# stm32-2inch40-usb-sd.net
KiCad netlist of a schematic drawn in EAGLE
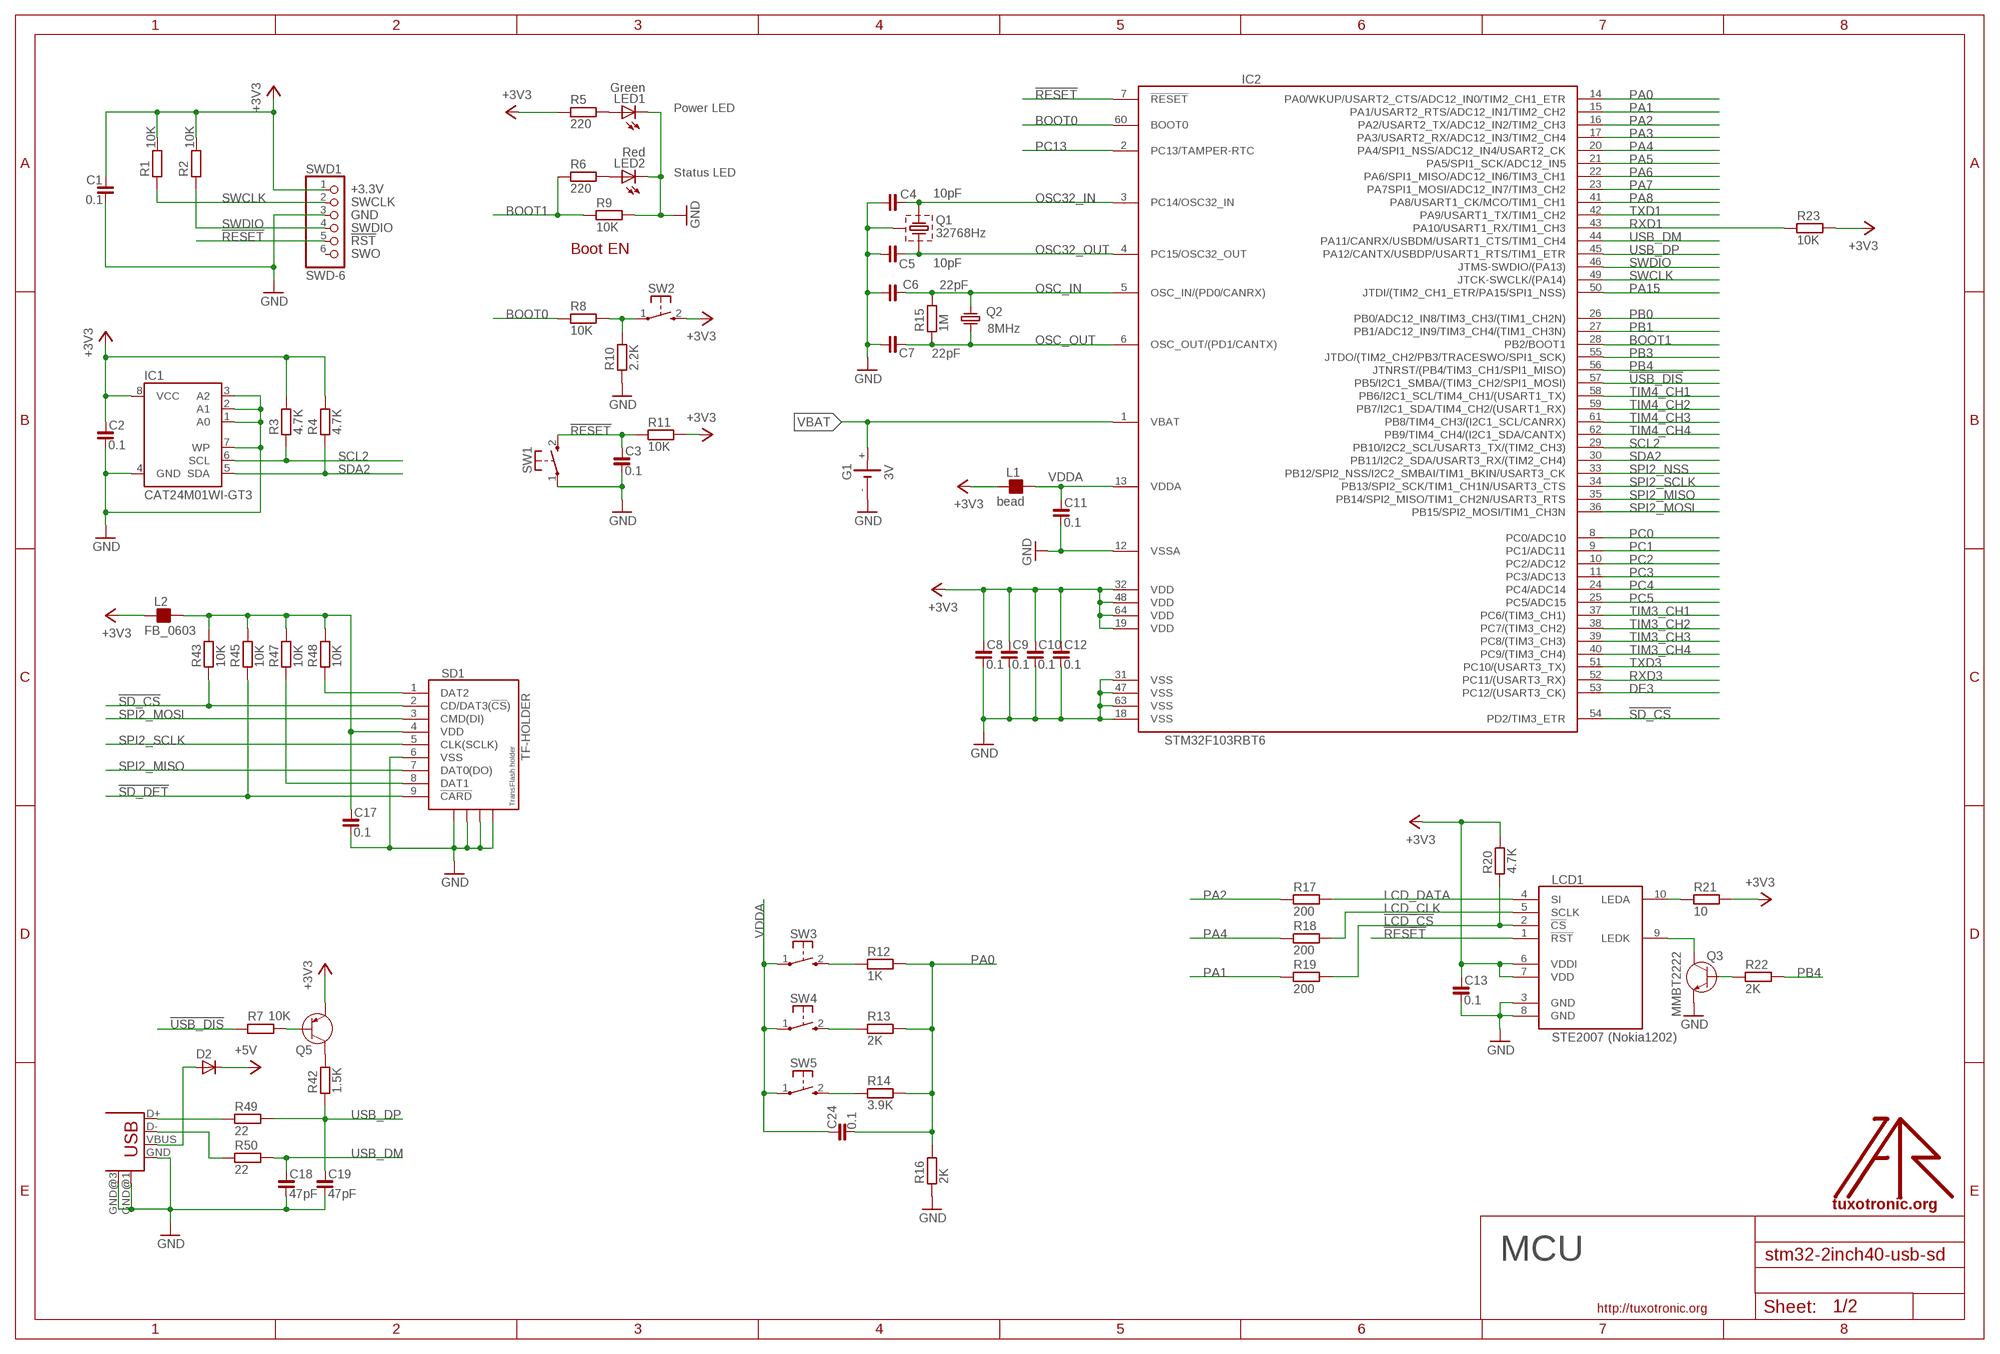
[diagram p0: schematic, sheet 1]
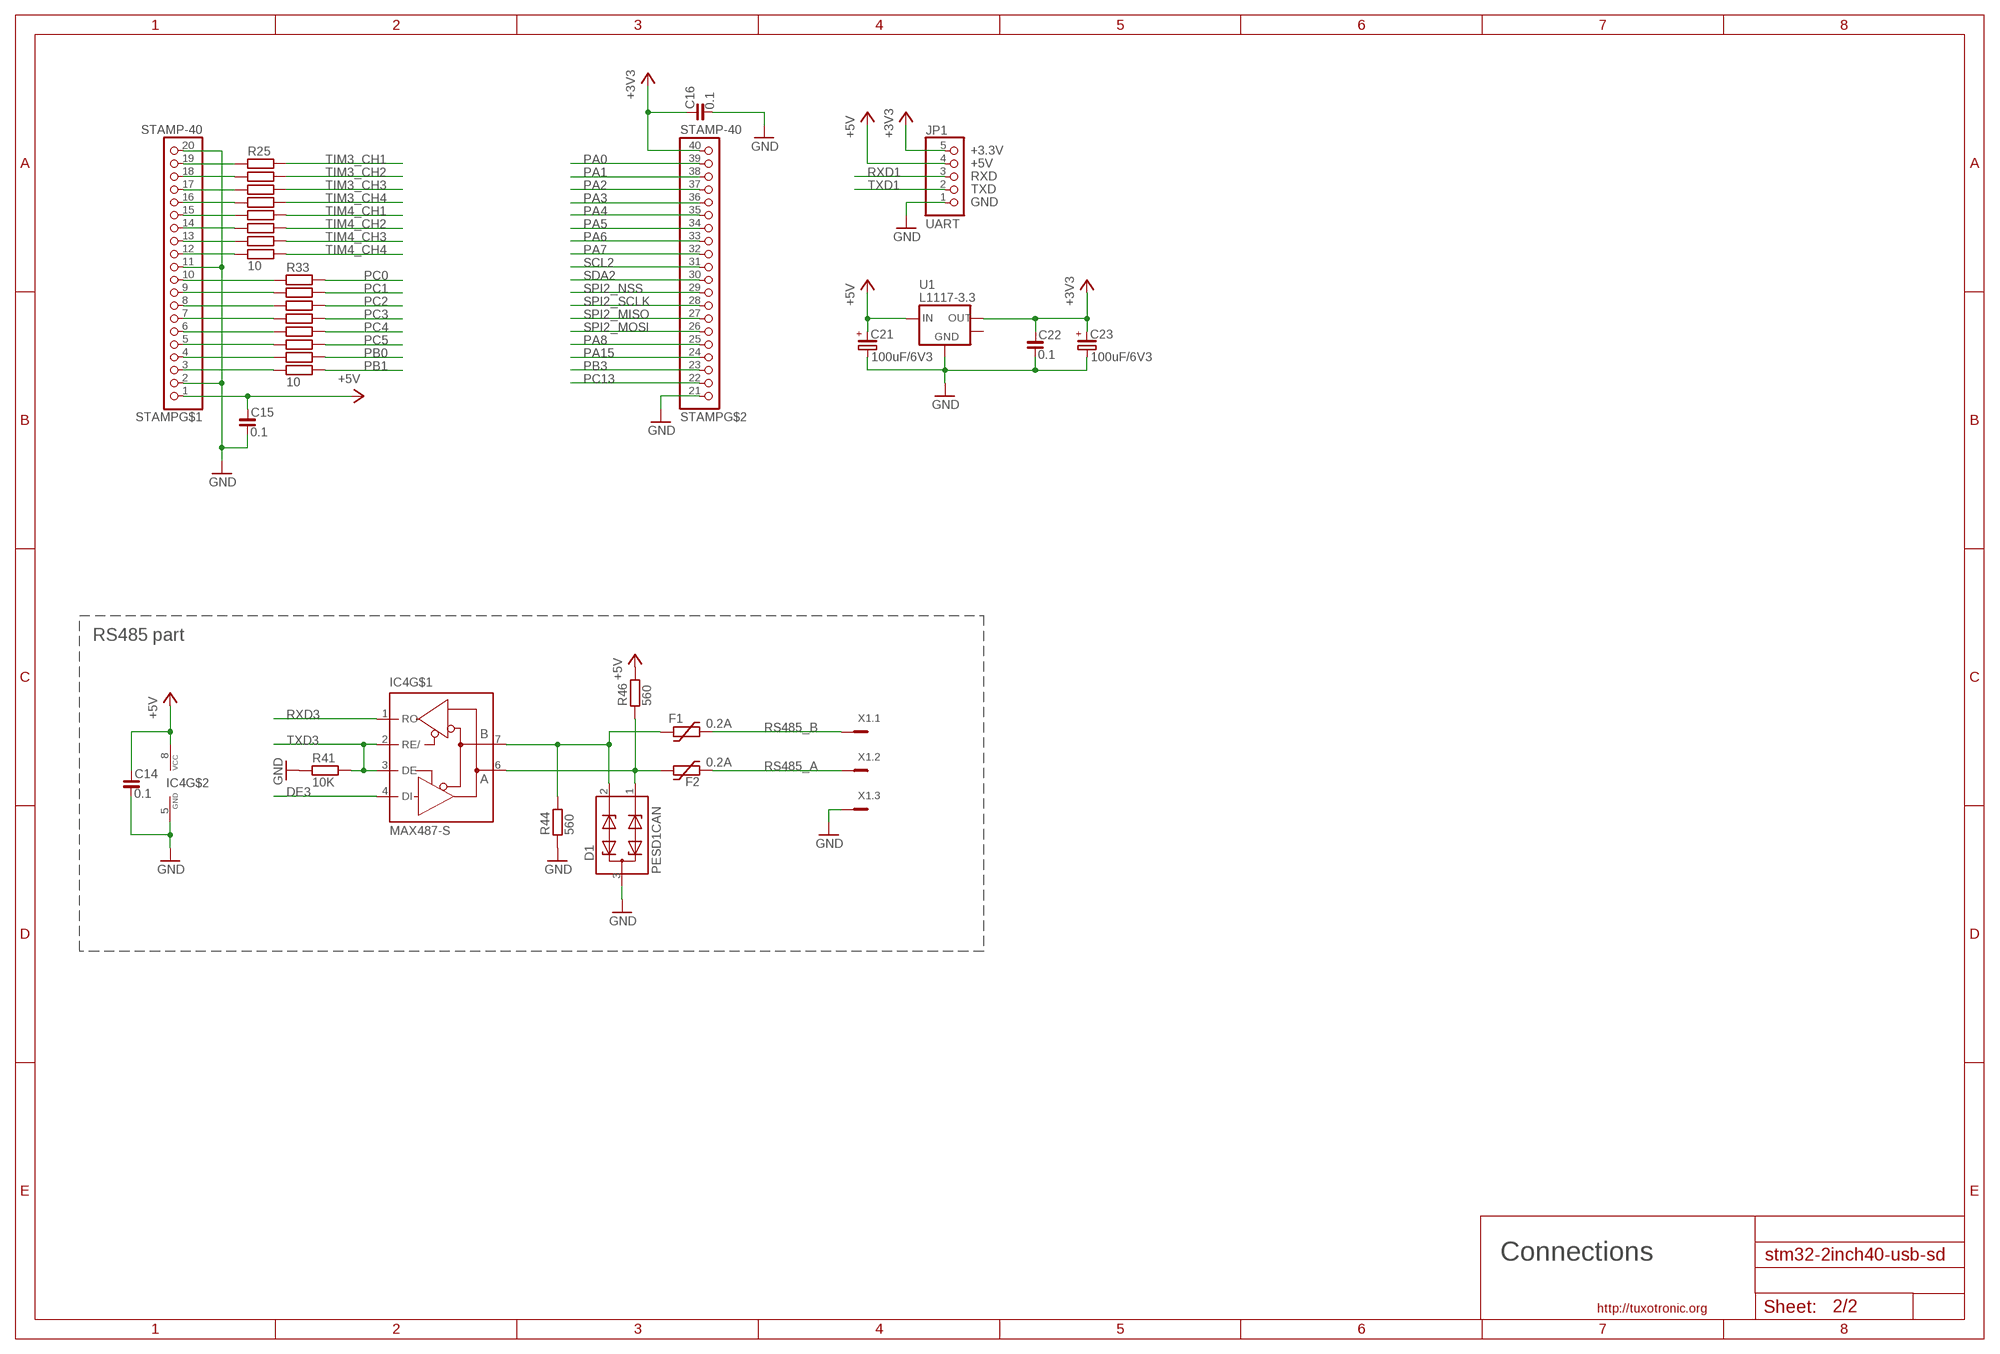
[diagram p1: schematic, sheet 2]

(export (version "E")
  (design (tool "Eeschema 10.0.6"))
  (components
    (comp (ref "C14")
      (value "0.1")
      (footprint "eagle-import:C0603")
      (libsource (lib "eagle-import") (part "C_0603"))
    )
    (comp (ref "C15")
      (value "0.1")
      (footprint "eagle-import:C0805")
      (libsource (lib "eagle-import") (part "C_0805"))
    )
    (comp (ref "C16")
      (value "0.1")
      (footprint "eagle-import:C0805")
      (libsource (lib "eagle-import") (part "C_0805"))
    )
    (comp (ref "C21")
      (value "100uF/6V3")
      (footprint "eagle-import:SMC_D")
      (libsource (lib "eagle-import") (part "CP_SMCD"))
    )
    (comp (ref "C22")
      (value "0.1")
      (footprint "eagle-import:C0805")
      (libsource (lib "eagle-import") (part "C_0805"))
    )
    (comp (ref "C23")
      (value "100uF/6V3")
      (footprint "eagle-import:SMC_D")
      (libsource (lib "eagle-import") (part "CP_SMCD"))
    )
    (comp (ref "D1")
      (value "PESD1CAN")
      (footprint "eagle-import:SOT23")
      (libsource (lib "eagle-import") (part "PESD1CAN"))
    )
    (comp (ref "F1")
      (value "0.2A")
      (footprint "eagle-import:1206L")
      (libsource (lib "eagle-import") (part "1206L"))
    )
    (comp (ref "F2")
      (value "0.2A")
      (footprint "eagle-import:1206L")
      (libsource (lib "eagle-import") (part "1206L"))
    )
    (comp (ref "IC4")
      (value "MAX487-S")
      (footprint "eagle-import:SO08")
      (libsource (lib "eagle-import") (part "MAX487-S"))
    )
    (comp (ref "JP1")
      (value "UART")
      (footprint "eagle-import:UART_1X05")
      (libsource (lib "eagle-import") (part "UART-5_2.54"))
    )
    (comp (ref "R25")
      (value "10")
      (footprint "eagle-import:R0603")
      (libsource (lib "eagle-import") (part "R_0603"))
    )
    (comp (ref "R26")
      (value "10")
      (footprint "eagle-import:R0603")
      (libsource (lib "eagle-import") (part "R_0603"))
    )
    (comp (ref "R27")
      (value "10")
      (footprint "eagle-import:R0603")
      (libsource (lib "eagle-import") (part "R_0603"))
    )
    (comp (ref "R28")
      (value "10")
      (footprint "eagle-import:R0603")
      (libsource (lib "eagle-import") (part "R_0603"))
    )
    (comp (ref "R29")
      (value "10")
      (footprint "eagle-import:R0603")
      (libsource (lib "eagle-import") (part "R_0603"))
    )
    (comp (ref "R30")
      (value "10")
      (footprint "eagle-import:R0603")
      (libsource (lib "eagle-import") (part "R_0603"))
    )
    (comp (ref "R31")
      (value "10")
      (footprint "eagle-import:R0603")
      (libsource (lib "eagle-import") (part "R_0603"))
    )
    (comp (ref "R32")
      (value "10")
      (footprint "eagle-import:R0603")
      (libsource (lib "eagle-import") (part "R_0603"))
    )
    (comp (ref "R33")
      (value "10")
      (footprint "eagle-import:R0603")
      (libsource (lib "eagle-import") (part "R_0603"))
    )
    (comp (ref "R34")
      (value "10")
      (footprint "eagle-import:R0603")
      (libsource (lib "eagle-import") (part "R_0603"))
    )
    (comp (ref "R35")
      (value "10")
      (footprint "eagle-import:R0603")
      (libsource (lib "eagle-import") (part "R_0603"))
    )
    (comp (ref "R36")
      (value "10")
      (footprint "eagle-import:R0603")
      (libsource (lib "eagle-import") (part "R_0603"))
    )
    (comp (ref "R37")
      (value "10")
      (footprint "eagle-import:R0603")
      (libsource (lib "eagle-import") (part "R_0603"))
    )
    (comp (ref "R38")
      (value "10")
      (footprint "eagle-import:R0603")
      (libsource (lib "eagle-import") (part "R_0603"))
    )
    (comp (ref "R39")
      (value "10")
      (footprint "eagle-import:R0603")
      (libsource (lib "eagle-import") (part "R_0603"))
    )
    (comp (ref "R40")
      (value "10")
      (footprint "eagle-import:R0603")
      (libsource (lib "eagle-import") (part "R_0603"))
    )
    (comp (ref "R41")
      (value "10K")
      (footprint "eagle-import:R0603")
      (libsource (lib "eagle-import") (part "R_0603"))
    )
    (comp (ref "R44")
      (value "560")
      (footprint "eagle-import:R0603")
      (libsource (lib "eagle-import") (part "R_0603"))
    )
    (comp (ref "R46")
      (value "560")
      (footprint "eagle-import:R0603")
      (libsource (lib "eagle-import") (part "R_0603"))
    )
    (comp (ref "STAMP")
      (value "STAMP-40")
      (footprint "eagle-import:STAMP-40")
      (libsource (lib "eagle-import") (part "STAMP-40"))
    )
    (comp (ref "U1")
      (value "L1117-3.3")
      (footprint "eagle-import:SOT223")
      (libsource (lib "eagle-import") (part "LM1117-3.3"))
    )
    (comp (ref "X1")
      (value "MCV3")
      (footprint "eagle-import:MCV3")
      (libsource (lib "eagle-import") (part "MCV3"))
    )
    (comp (ref "C1")
      (value "0.1")
      (footprint "eagle-import:C0603")
      (libsource (lib "eagle-import") (part "C_0603"))
    )
    (comp (ref "C2")
      (value "0.1")
      (footprint "eagle-import:C0603")
      (libsource (lib "eagle-import") (part "C_0603"))
    )
    (comp (ref "C3")
      (value "0.1")
      (footprint "eagle-import:C0603")
      (libsource (lib "eagle-import") (part "C_0603"))
    )
    (comp (ref "C4")
      (value "10pF")
      (footprint "eagle-import:C0603")
      (libsource (lib "eagle-import") (part "C_0603"))
    )
    (comp (ref "C5")
      (value "10pF")
      (footprint "eagle-import:C0603")
      (libsource (lib "eagle-import") (part "C_0603"))
    )
    (comp (ref "C6")
      (value "22pF")
      (footprint "eagle-import:C0603")
      (libsource (lib "eagle-import") (part "C_0603"))
    )
    (comp (ref "C7")
      (value "22pF")
      (footprint "eagle-import:C0603")
      (libsource (lib "eagle-import") (part "C_0603"))
    )
    (comp (ref "C8")
      (value "0.1")
      (footprint "eagle-import:C0603")
      (libsource (lib "eagle-import") (part "C_0603"))
    )
    (comp (ref "C9")
      (value "0.1")
      (footprint "eagle-import:C0603")
      (libsource (lib "eagle-import") (part "C_0603"))
    )
    (comp (ref "C10")
      (value "0.1")
      (footprint "eagle-import:C0603")
      (libsource (lib "eagle-import") (part "C_0603"))
    )
    (comp (ref "C11")
      (value "0.1")
      (footprint "eagle-import:C0603")
      (libsource (lib "eagle-import") (part "C_0603"))
    )
    (comp (ref "C12")
      (value "0.1")
      (footprint "eagle-import:C0603")
      (libsource (lib "eagle-import") (part "C_0603"))
    )
    (comp (ref "C13")
      (value "0.1")
      (footprint "eagle-import:C0603")
      (libsource (lib "eagle-import") (part "C_0603"))
    )
    (comp (ref "C17")
      (value "0.1")
      (footprint "eagle-import:C0603")
      (libsource (lib "eagle-import") (part "C_0603"))
    )
    (comp (ref "C18")
      (value "47pF")
      (footprint "eagle-import:C0603")
      (libsource (lib "eagle-import") (part "C_0603"))
    )
    (comp (ref "C19")
      (value "47pF")
      (footprint "eagle-import:C0603")
      (libsource (lib "eagle-import") (part "C_0603"))
    )
    (comp (ref "C24")
      (value "0.1")
      (footprint "eagle-import:C0603")
      (libsource (lib "eagle-import") (part "C_0603"))
    )
    (comp (ref "D2")
      (value "D-SOD-87")
      (footprint "eagle-import:SOD87")
      (libsource (lib "eagle-import") (part "D-SOD-87"))
    )
    (comp (ref "G1")
      (value "3V")
      (footprint "eagle-import:SMT1220")
      (libsource (lib "eagle-import") (part "1220SMT"))
    )
    (comp (ref "IC1")
      (value "CAT24M01WI-GT3")
      (footprint "eagle-import:SO08")
      (libsource (lib "eagle-import") (part "AT24CS256"))
    )
    (comp (ref "IC2")
      (value "STM32F103RBT6")
      (footprint "eagle-import:TQFP64")
      (libsource (lib "eagle-import") (part "STM32F103R"))
    )
    (comp (ref "L1")
      (value "bead")
      (footprint "eagle-import:L0603")
      (libsource (lib "eagle-import") (part "FB_0603"))
    )
    (comp (ref "L2")
      (value "FB_0603")
      (footprint "eagle-import:L0603")
      (libsource (lib "eagle-import") (part "FB_0603"))
    )
    (comp (ref "LCD1")
      (value "STE2007 (Nokia1202)")
      (footprint "eagle-import:NOKIA1202LCD-EXT")
      (libsource (lib "eagle-import") (part "LCD1202-EXT"))
    )
    (comp (ref "LED1")
      (value "Green")
      (footprint "eagle-import:CHIP-LED0805")
      (libsource (lib "eagle-import") (part "LEDCHIP-LED0805"))
    )
    (comp (ref "LED2")
      (value "Red")
      (footprint "eagle-import:CHIP-LED0805")
      (libsource (lib "eagle-import") (part "LEDCHIP-LED0805"))
    )
    (comp (ref "Q1")
      (value "32768Hz")
      (footprint "eagle-import:TC38H-G")
      (libsource (lib "eagle-import") (part "CRSTL3-"))
    )
    (comp (ref "Q2")
      (value "8MHz")
      (footprint "eagle-import:HC49_S")
      (libsource (lib "eagle-import") (part "CRYSTAL-HC49S"))
    )
    (comp (ref "Q3")
      (value "MMBT2222")
      (footprint "eagle-import:SOT23")
      (libsource (lib "eagle-import") (part "MMBT2222"))
    )
    (comp (ref "Q5")
      (value "PNP-SOT23")
      (footprint "eagle-import:SOT23")
      (libsource (lib "eagle-import") (part "PNP-SOT23"))
    )
    (comp (ref "R1")
      (value "10K")
      (footprint "eagle-import:R0603")
      (libsource (lib "eagle-import") (part "R_0603"))
    )
    (comp (ref "R2")
      (value "10K")
      (footprint "eagle-import:R0603")
      (libsource (lib "eagle-import") (part "R_0603"))
    )
    (comp (ref "R3")
      (value "4.7K")
      (footprint "eagle-import:R0603")
      (libsource (lib "eagle-import") (part "R_0603"))
    )
    (comp (ref "R4")
      (value "4.7K")
      (footprint "eagle-import:R0603")
      (libsource (lib "eagle-import") (part "R_0603"))
    )
    (comp (ref "R5")
      (value "220")
      (footprint "eagle-import:R0603")
      (libsource (lib "eagle-import") (part "R_0603"))
    )
    (comp (ref "R6")
      (value "220")
      (footprint "eagle-import:R0603")
      (libsource (lib "eagle-import") (part "R_0603"))
    )
    (comp (ref "R7")
      (value "10K")
      (footprint "eagle-import:R0603")
      (libsource (lib "eagle-import") (part "R_0603"))
    )
    (comp (ref "R8")
      (value "10K")
      (footprint "eagle-import:R0603")
      (libsource (lib "eagle-import") (part "R_0603"))
    )
    (comp (ref "R9")
      (value "10K")
      (footprint "eagle-import:R0603")
      (libsource (lib "eagle-import") (part "R_0603"))
    )
    (comp (ref "R10")
      (value "2.2K")
      (footprint "eagle-import:R0603")
      (libsource (lib "eagle-import") (part "R_0603"))
    )
    (comp (ref "R11")
      (value "10K")
      (footprint "eagle-import:R0603")
      (libsource (lib "eagle-import") (part "R_0603"))
    )
    (comp (ref "R12")
      (value "1K")
      (footprint "eagle-import:R0603")
      (libsource (lib "eagle-import") (part "R_0603"))
    )
    (comp (ref "R13")
      (value "2K")
      (footprint "eagle-import:R0603")
      (libsource (lib "eagle-import") (part "R_0603"))
    )
    (comp (ref "R14")
      (value "3.9K")
      (footprint "eagle-import:R0603")
      (libsource (lib "eagle-import") (part "R_0603"))
    )
    (comp (ref "R15")
      (value "1M")
      (footprint "eagle-import:R0603")
      (libsource (lib "eagle-import") (part "R_0603"))
    )
    (comp (ref "R16")
      (value "2K")
      (footprint "eagle-import:R0603")
      (libsource (lib "eagle-import") (part "R_0603"))
    )
    (comp (ref "R17")
      (value "200")
      (footprint "eagle-import:R0603")
      (libsource (lib "eagle-import") (part "R_0603"))
    )
    (comp (ref "R18")
      (value "200")
      (footprint "eagle-import:R0603")
      (libsource (lib "eagle-import") (part "R_0603"))
    )
    (comp (ref "R19")
      (value "200")
      (footprint "eagle-import:R0603")
      (libsource (lib "eagle-import") (part "R_0603"))
    )
    (comp (ref "R20")
      (value "4.7K")
      (footprint "eagle-import:R0603")
      (libsource (lib "eagle-import") (part "R_0603"))
    )
    (comp (ref "R21")
      (value "10")
      (footprint "eagle-import:R0603")
      (libsource (lib "eagle-import") (part "R_0603"))
    )
    (comp (ref "R22")
      (value "2K")
      (footprint "eagle-import:R0603")
      (libsource (lib "eagle-import") (part "R_0603"))
    )
    (comp (ref "R23")
      (value "10K")
      (footprint "eagle-import:R0603")
      (libsource (lib "eagle-import") (part "R_0603"))
    )
    (comp (ref "R42")
      (value "1.5K")
      (footprint "eagle-import:R0603")
      (libsource (lib "eagle-import") (part "R_0603"))
    )
    (comp (ref "R43")
      (value "10K")
      (footprint "eagle-import:R0603")
      (libsource (lib "eagle-import") (part "R_0603"))
    )
    (comp (ref "R45")
      (value "10K")
      (footprint "eagle-import:R0603")
      (libsource (lib "eagle-import") (part "R_0603"))
    )
    (comp (ref "R47")
      (value "10K")
      (footprint "eagle-import:R0603")
      (libsource (lib "eagle-import") (part "R_0603"))
    )
    (comp (ref "R48")
      (value "10K")
      (footprint "eagle-import:R0603")
      (libsource (lib "eagle-import") (part "R_0603"))
    )
    (comp (ref "R49")
      (value "22")
      (footprint "eagle-import:R0603")
      (libsource (lib "eagle-import") (part "R_0603"))
    )
    (comp (ref "R50")
      (value "22")
      (footprint "eagle-import:R0603")
      (libsource (lib "eagle-import") (part "R_0603"))
    )
    (comp (ref "SD1")
      (value "TF-HOLDER")
      (footprint "eagle-import:TF-PULL")
      (libsource (lib "eagle-import") (part "TF-HOLDER"))
    )
    (comp (ref "SW1")
      (value "KSS-2EG4430")
      (footprint "eagle-import:KSS-2EG4430")
      (libsource (lib "eagle-import") (part "KSS-2EG4430"))
    )
    (comp (ref "SW2")
      (value "KSS-2EG4430")
      (footprint "eagle-import:KSS-2EG4430")
      (libsource (lib "eagle-import") (part "KSS-2EG4430"))
    )
    (comp (ref "SW3")
      (value "KSS-2EG4430")
      (footprint "eagle-import:KSS-2EG4430")
      (libsource (lib "eagle-import") (part "KSS-2EG4430"))
    )
    (comp (ref "SW4")
      (value "KSS-2EG4430")
      (footprint "eagle-import:KSS-2EG4430")
      (libsource (lib "eagle-import") (part "KSS-2EG4430"))
    )
    (comp (ref "SW5")
      (value "KSS-2EG4430")
      (footprint "eagle-import:KSS-2EG4430")
      (libsource (lib "eagle-import") (part "KSS-2EG4430"))
    )
    (comp (ref "SWD1")
      (value "SWD-6")
      (footprint "eagle-import:JTAG6PIN")
      (libsource (lib "eagle-import") (part "SWD-6"))
    )
    (comp (ref "U$1")
      (value "LOGO")
      (footprint "eagle-import:TT_LOGO")
      (libsource (lib "eagle-import") (part "LOGO"))
    )
    (comp (ref "USB1")
      (value "USB-MB-S")
      (footprint "eagle-import:USB-MB-S")
      (libsource (lib "eagle-import") (part "USB-MB-S"))
    )
  )
  (nets
    (net (code "1") (name "+3V3") (class "Default")
      (node (ref "C1") (pin "1") (pinfunction "1_1") (pintype "passive"))
      (node (ref "C10") (pin "1") (pinfunction "1_1") (pintype "passive"))
      (node (ref "C12") (pin "1") (pinfunction "1_1") (pintype "passive"))
      (node (ref "C13") (pin "1") (pinfunction "1_1") (pintype "passive"))
      (node (ref "C16") (pin "1") (pinfunction "1_1") (pintype "passive"))
      (node (ref "C2") (pin "1") (pinfunction "1_1") (pintype "passive"))
      (node (ref "C22") (pin "1") (pinfunction "1_1") (pintype "passive"))
      (node (ref "C23") (pin "+") (pinfunction "+_+") (pintype "passive"))
      (node (ref "C8") (pin "1") (pinfunction "1_1") (pintype "passive"))
      (node (ref "C9") (pin "1") (pinfunction "1_1") (pintype "passive"))
      (node (ref "IC1") (pin "8") (pinfunction "VCC_8") (pintype "power_in"))
      (node (ref "IC2") (pin "19") (pinfunction "VDD_19") (pintype "power_in"))
      (node (ref "IC2") (pin "32") (pinfunction "VDD_32") (pintype "power_in"))
      (node (ref "IC2") (pin "48") (pinfunction "VDD_48") (pintype "power_in"))
      (node (ref "IC2") (pin "64") (pinfunction "VDD_64") (pintype "power_in"))
      (node (ref "JP1") (pin "5") (pinfunction "5_5") (pintype "passive"))
      (node (ref "L1") (pin "1") (pinfunction "1_1") (pintype "passive"))
      (node (ref "L2") (pin "1") (pinfunction "1_1") (pintype "passive"))
      (node (ref "LCD1") (pin "6") (pinfunction "VDDI_6") (pintype "power_in"))
      (node (ref "LCD1") (pin "7") (pinfunction "VDD_7") (pintype "power_in"))
      (node (ref "Q5") (pin "2") (pinfunction "E_2") (pintype "passive"))
      (node (ref "R1") (pin "2") (pinfunction "2_2") (pintype "passive"))
      (node (ref "R11") (pin "2") (pinfunction "2_2") (pintype "passive"))
      (node (ref "R2") (pin "2") (pinfunction "2_2") (pintype "passive"))
      (node (ref "R20") (pin "2") (pinfunction "2_2") (pintype "passive"))
      (node (ref "R21") (pin "2") (pinfunction "2_2") (pintype "passive"))
      (node (ref "R23") (pin "2") (pinfunction "2_2") (pintype "passive"))
      (node (ref "R3") (pin "2") (pinfunction "2_2") (pintype "passive"))
      (node (ref "R4") (pin "2") (pinfunction "2_2") (pintype "passive"))
      (node (ref "R5") (pin "1") (pinfunction "1_1") (pintype "passive"))
      (node (ref "STAMP") (pin "40") (pinfunction "20_40") (pintype "passive"))
      (node (ref "SW2") (pin "2") (pinfunction "S_2") (pintype "passive"))
      (node (ref "SWD1") (pin "1") (pinfunction "1_1") (pintype "passive"))
      (node (ref "U1") (pin "2") (pinfunction "OUT_2") (pintype "power_in"))
    )
    (net (code "2") (name "+5V") (class "Default")
      (node (ref "C14") (pin "1") (pinfunction "1_1") (pintype "passive"))
      (node (ref "C15") (pin "1") (pinfunction "1_1") (pintype "passive"))
      (node (ref "C21") (pin "+") (pinfunction "+_+") (pintype "passive"))
      (node (ref "D2") (pin "1") (pinfunction "C_1") (pintype "passive"))
      (node (ref "IC4") (pin "8") (pinfunction "VCC_8") (pintype "power_in"))
      (node (ref "JP1") (pin "4") (pinfunction "4_4") (pintype "passive"))
      (node (ref "R46") (pin "2") (pinfunction "2_2") (pintype "passive"))
      (node (ref "STAMP") (pin "1") (pinfunction "1_1") (pintype "passive"))
      (node (ref "U1") (pin "3") (pinfunction "IN_3") (pintype "power_in"))
    )
    (net (code "3") (name "BOOT0") (class "Default")
      (node (ref "IC2") (pin "60") (pinfunction "BOOT0_60") (pintype "input"))
      (node (ref "R8") (pin "1") (pinfunction "1_1") (pintype "passive"))
    )
    (net (code "4") (name "BOOT1") (class "Default")
      (node (ref "IC2") (pin "28") (pinfunction "PB2/BOOT1_28") (pintype "bidirectional"))
      (node (ref "R6") (pin "1") (pinfunction "1_1") (pintype "passive"))
      (node (ref "R9") (pin "1") (pinfunction "1_1") (pintype "passive"))
    )
    (net (code "5") (name "DE3") (class "Default")
      (node (ref "IC2") (pin "53") (pinfunction "PC12/(USART3_CK)_53") (pintype "bidirectional"))
      (node (ref "IC4") (pin "4") (pinfunction "DI_4") (pintype "input"))
    )
    (net (code "6") (name "GND") (class "Default")
      (node (ref "C1") (pin "2") (pinfunction "2_2") (pintype "passive"))
      (node (ref "C10") (pin "2") (pinfunction "2_2") (pintype "passive"))
      (node (ref "C11") (pin "2") (pinfunction "2_2") (pintype "passive"))
      (node (ref "C12") (pin "2") (pinfunction "2_2") (pintype "passive"))
      (node (ref "C13") (pin "2") (pinfunction "2_2") (pintype "passive"))
      (node (ref "C14") (pin "2") (pinfunction "2_2") (pintype "passive"))
      (node (ref "C15") (pin "2") (pinfunction "2_2") (pintype "passive"))
      (node (ref "C16") (pin "2") (pinfunction "2_2") (pintype "passive"))
      (node (ref "C17") (pin "2") (pinfunction "2_2") (pintype "passive"))
      (node (ref "C18") (pin "2") (pinfunction "2_2") (pintype "passive"))
      (node (ref "C19") (pin "2") (pinfunction "2_2") (pintype "passive"))
      (node (ref "C2") (pin "2") (pinfunction "2_2") (pintype "passive"))
      (node (ref "C21") (pin "-") (pinfunction "-_-") (pintype "passive"))
      (node (ref "C22") (pin "2") (pinfunction "2_2") (pintype "passive"))
      (node (ref "C23") (pin "-") (pinfunction "-_-") (pintype "passive"))
      (node (ref "C3") (pin "2") (pinfunction "2_2") (pintype "passive"))
      (node (ref "C4") (pin "2") (pinfunction "2_2") (pintype "passive"))
      (node (ref "C5") (pin "2") (pinfunction "2_2") (pintype "passive"))
      (node (ref "C6") (pin "2") (pinfunction "2_2") (pintype "passive"))
      (node (ref "C7") (pin "2") (pinfunction "2_2") (pintype "passive"))
      (node (ref "C8") (pin "2") (pinfunction "2_2") (pintype "passive"))
      (node (ref "C9") (pin "2") (pinfunction "2_2") (pintype "passive"))
      (node (ref "D1") (pin "3") (pinfunction "3_3") (pintype "passive"))
      (node (ref "G1") (pin "-") (pinfunction "-_-") (pintype "passive"))
      (node (ref "IC1") (pin "1") (pinfunction "A0_1") (pintype "input"))
      (node (ref "IC1") (pin "2") (pinfunction "A1_2") (pintype "input"))
      (node (ref "IC1") (pin "3") (pinfunction "A2_3") (pintype "input"))
      (node (ref "IC1") (pin "4") (pinfunction "GND_4") (pintype "power_in"))
      (node (ref "IC1") (pin "7") (pinfunction "WP_7") (pintype "input"))
      (node (ref "IC2") (pin "12") (pinfunction "VSSA_12") (pintype "power_in"))
      (node (ref "IC2") (pin "18") (pinfunction "VSS_18") (pintype "power_in"))
      (node (ref "IC2") (pin "31") (pinfunction "VSS_31") (pintype "power_in"))
      (node (ref "IC2") (pin "47") (pinfunction "VSS_47") (pintype "power_in"))
      (node (ref "IC2") (pin "63") (pinfunction "VSS_63") (pintype "power_in"))
      (node (ref "IC4") (pin "5") (pinfunction "GND_5") (pintype "power_in"))
      (node (ref "JP1") (pin "1") (pinfunction "1_1") (pintype "passive"))
      (node (ref "LCD1") (pin "3") (pinfunction "GND_3") (pintype "power_in"))
      (node (ref "LCD1") (pin "8") (pinfunction "GND_8") (pintype "power_in"))
      (node (ref "LED1") (pin "C") (pinfunction "C_C") (pintype "passive"))
      (node (ref "LED2") (pin "C") (pinfunction "C_C") (pintype "passive"))
      (node (ref "Q1") (pin "GND") (pinfunction "P$1_GND") (pintype "passive"))
      (node (ref "Q3") (pin "2") (pinfunction "E_2") (pintype "passive"))
      (node (ref "R10") (pin "1") (pinfunction "1_1") (pintype "passive"))
      (node (ref "R16") (pin "1") (pinfunction "1_1") (pintype "passive"))
      (node (ref "R41") (pin "1") (pinfunction "1_1") (pintype "passive"))
      (node (ref "R44") (pin "1") (pinfunction "1_1") (pintype "passive"))
      (node (ref "R9") (pin "2") (pinfunction "2_2") (pintype "passive"))
      (node (ref "SD1") (pin "6") (pinfunction "VSS_6") (pintype "power_in"))
      (node (ref "SD1") (pin "S1") (pinfunction "S1_S1") (pintype "passive"))
      (node (ref "SD1") (pin "S2") (pinfunction "S2_S2") (pintype "passive"))
      (node (ref "SD1") (pin "S3") (pinfunction "S3_S3") (pintype "passive"))
      (node (ref "SD1") (pin "S4") (pinfunction "S4_S4") (pintype "passive"))
      (node (ref "STAMP") (pin "11") (pinfunction "11_11") (pintype "passive"))
      (node (ref "STAMP") (pin "2") (pinfunction "2_2") (pintype "passive"))
      (node (ref "STAMP") (pin "20") (pinfunction "20_20") (pintype "passive"))
      (node (ref "STAMP") (pin "21") (pinfunction "1_21") (pintype "passive"))
      (node (ref "SW1") (pin "1") (pinfunction "P_1") (pintype "passive"))
      (node (ref "SWD1") (pin "3") (pinfunction "3_3") (pintype "passive"))
      (node (ref "U1") (pin "1") (pinfunction "GND_1") (pintype "power_in"))
      (node (ref "USB1") (pin "GND") (pinfunction "GND_GND") (pintype "bidirectional"))
      (node (ref "USB1") (pin "GND@1") (pinfunction "GND_GND@1") (pintype "bidirectional"))
      (node (ref "USB1") (pin "GND@3") (pinfunction "GND_GND@3") (pintype "bidirectional"))
      (node (ref "X1") (pin "3") (pinfunction "SK_3") (pintype "passive"))
    )
    (net (code "7") (name "LCD_CLK") (class "Default")
      (node (ref "LCD1") (pin "5") (pinfunction "SCLK_5") (pintype "input"))
      (node (ref "R18") (pin "2") (pinfunction "2_2") (pintype "passive"))
    )
    (net (code "8") (name "LCD_DATA") (class "Default")
      (node (ref "LCD1") (pin "4") (pinfunction "SI_4") (pintype "input"))
      (node (ref "R17") (pin "2") (pinfunction "2_2") (pintype "passive"))
    )
    (net (code "9") (name "Net-(D2-A)") (class "Default")
      (node (ref "D2") (pin "2") (pinfunction "A_2") (pintype "passive"))
      (node (ref "USB1") (pin "VBUS") (pinfunction "VBUS_VBUS") (pintype "bidirectional"))
    )
    (net (code "10") (name "Net-(F1-1)") (class "Default")
      (node (ref "D1") (pin "2") (pinfunction "2_2") (pintype "passive"))
      (node (ref "F1") (pin "P$1") (pinfunction "1_P$1") (pintype "passive"))
      (node (ref "IC4") (pin "7") (pinfunction "B_7") (pintype "passive"))
      (node (ref "R44") (pin "2") (pinfunction "2_2") (pintype "passive"))
    )
    (net (code "11") (name "Net-(F2-1)") (class "Default")
      (node (ref "D1") (pin "1") (pinfunction "1_1") (pintype "passive"))
      (node (ref "F2") (pin "P$1") (pinfunction "1_P$1") (pintype "passive"))
      (node (ref "IC4") (pin "6") (pinfunction "A_6") (pintype "passive"))
      (node (ref "R46") (pin "1") (pinfunction "1_1") (pintype "passive"))
    )
    (net (code "12") (name "Net-(LCD1-LEDA)") (class "Default")
      (node (ref "LCD1") (pin "10") (pinfunction "LEDA_10") (pintype "passive"))
      (node (ref "R21") (pin "1") (pinfunction "1_1") (pintype "passive"))
    )
    (net (code "13") (name "Net-(LCD1-LEDK)") (class "Default")
      (node (ref "LCD1") (pin "9") (pinfunction "LEDK_9") (pintype "passive"))
      (node (ref "Q3") (pin "3") (pinfunction "C_3") (pintype "passive"))
    )
    (net (code "14") (name "Net-(LED1-PadA)") (class "Default")
      (node (ref "LED1") (pin "A") (pinfunction "A_A") (pintype "passive"))
      (node (ref "R5") (pin "2") (pinfunction "2_2") (pintype "passive"))
    )
    (net (code "15") (name "Net-(LED2-PadA)") (class "Default")
      (node (ref "LED2") (pin "A") (pinfunction "A_A") (pintype "passive"))
      (node (ref "R6") (pin "2") (pinfunction "2_2") (pintype "passive"))
    )
    (net (code "16") (name "Net-(Q3-B)") (class "Default")
      (node (ref "Q3") (pin "1") (pinfunction "B_1") (pintype "passive"))
      (node (ref "R22") (pin "1") (pinfunction "1_1") (pintype "passive"))
    )
    (net (code "17") (name "Net-(Q5-B)") (class "Default")
      (node (ref "Q5") (pin "1") (pinfunction "B_1") (pintype "passive"))
      (node (ref "R7") (pin "2") (pinfunction "2_2") (pintype "passive"))
    )
    (net (code "18") (name "Net-(Q5-C)") (class "Default")
      (node (ref "Q5") (pin "3") (pinfunction "C_3") (pintype "passive"))
      (node (ref "R42") (pin "2") (pinfunction "2_2") (pintype "passive"))
    )
    (net (code "19") (name "Net-(R25-Pad1)") (class "Default")
      (node (ref "R25") (pin "1") (pinfunction "1_1") (pintype "passive"))
      (node (ref "STAMP") (pin "19") (pinfunction "19_19") (pintype "passive"))
    )
    (net (code "20") (name "Net-(R26-Pad1)") (class "Default")
      (node (ref "R26") (pin "1") (pinfunction "1_1") (pintype "passive"))
      (node (ref "STAMP") (pin "18") (pinfunction "18_18") (pintype "passive"))
    )
    (net (code "21") (name "Net-(R27-Pad1)") (class "Default")
      (node (ref "R27") (pin "1") (pinfunction "1_1") (pintype "passive"))
      (node (ref "STAMP") (pin "17") (pinfunction "17_17") (pintype "passive"))
    )
    (net (code "22") (name "Net-(R28-Pad1)") (class "Default")
      (node (ref "R28") (pin "1") (pinfunction "1_1") (pintype "passive"))
      (node (ref "STAMP") (pin "16") (pinfunction "16_16") (pintype "passive"))
    )
    (net (code "23") (name "Net-(R29-Pad1)") (class "Default")
      (node (ref "R29") (pin "1") (pinfunction "1_1") (pintype "passive"))
      (node (ref "STAMP") (pin "15") (pinfunction "15_15") (pintype "passive"))
    )
    (net (code "24") (name "Net-(R30-Pad1)") (class "Default")
      (node (ref "R30") (pin "1") (pinfunction "1_1") (pintype "passive"))
      (node (ref "STAMP") (pin "14") (pinfunction "14_14") (pintype "passive"))
    )
    (net (code "25") (name "Net-(R31-Pad1)") (class "Default")
      (node (ref "R31") (pin "1") (pinfunction "1_1") (pintype "passive"))
      (node (ref "STAMP") (pin "13") (pinfunction "13_13") (pintype "passive"))
    )
    (net (code "26") (name "Net-(R32-Pad1)") (class "Default")
      (node (ref "R32") (pin "1") (pinfunction "1_1") (pintype "passive"))
      (node (ref "STAMP") (pin "12") (pinfunction "12_12") (pintype "passive"))
    )
    (net (code "27") (name "Net-(R33-Pad1)") (class "Default")
      (node (ref "R33") (pin "1") (pinfunction "1_1") (pintype "passive"))
      (node (ref "STAMP") (pin "10") (pinfunction "10_10") (pintype "passive"))
    )
    (net (code "28") (name "Net-(R34-Pad1)") (class "Default")
      (node (ref "R34") (pin "1") (pinfunction "1_1") (pintype "passive"))
      (node (ref "STAMP") (pin "9") (pinfunction "9_9") (pintype "passive"))
    )
    (net (code "29") (name "Net-(R35-Pad1)") (class "Default")
      (node (ref "R35") (pin "1") (pinfunction "1_1") (pintype "passive"))
      (node (ref "STAMP") (pin "8") (pinfunction "8_8") (pintype "passive"))
    )
    (net (code "30") (name "Net-(R36-Pad1)") (class "Default")
      (node (ref "R36") (pin "1") (pinfunction "1_1") (pintype "passive"))
      (node (ref "STAMP") (pin "7") (pinfunction "7_7") (pintype "passive"))
    )
    (net (code "31") (name "Net-(R37-Pad1)") (class "Default")
      (node (ref "R37") (pin "1") (pinfunction "1_1") (pintype "passive"))
      (node (ref "STAMP") (pin "6") (pinfunction "6_6") (pintype "passive"))
    )
    (net (code "32") (name "Net-(R38-Pad1)") (class "Default")
      (node (ref "R38") (pin "1") (pinfunction "1_1") (pintype "passive"))
      (node (ref "STAMP") (pin "5") (pinfunction "5_5") (pintype "passive"))
    )
    (net (code "33") (name "Net-(R39-Pad1)") (class "Default")
      (node (ref "R39") (pin "1") (pinfunction "1_1") (pintype "passive"))
      (node (ref "STAMP") (pin "4") (pinfunction "4_4") (pintype "passive"))
    )
    (net (code "34") (name "Net-(R40-Pad1)") (class "Default")
      (node (ref "R40") (pin "1") (pinfunction "1_1") (pintype "passive"))
      (node (ref "STAMP") (pin "3") (pinfunction "3_3") (pintype "passive"))
    )
    (net (code "35") (name "Net-(R49-Pad1)") (class "Default")
      (node (ref "R49") (pin "1") (pinfunction "1_1") (pintype "passive"))
      (node (ref "USB1") (pin "D+") (pinfunction "D+_D+") (pintype "bidirectional"))
    )
    (net (code "36") (name "Net-(R50-Pad1)") (class "Default")
      (node (ref "R50") (pin "1") (pinfunction "1_1") (pintype "passive"))
      (node (ref "USB1") (pin "D-") (pinfunction "D-_D-") (pintype "bidirectional"))
    )
    (net (code "37") (name "Net-(SD1-DAT1)") (class "Default")
      (node (ref "R47") (pin "1") (pinfunction "1_1") (pintype "passive"))
      (node (ref "SD1") (pin "8") (pinfunction "DAT1_8") (pintype "bidirectional"))
    )
    (net (code "38") (name "Net-(SD1-DAT2)") (class "Default")
      (node (ref "R48") (pin "1") (pinfunction "1_1") (pintype "passive"))
      (node (ref "SD1") (pin "1") (pinfunction "DAT2_1") (pintype "bidirectional"))
    )
    (net (code "39") (name "Net-(SD1-VDD)") (class "Default")
      (node (ref "C17") (pin "1") (pinfunction "1_1") (pintype "passive"))
      (node (ref "L2") (pin "2") (pinfunction "2_2") (pintype "passive"))
      (node (ref "R43") (pin "2") (pinfunction "2_2") (pintype "passive"))
      (node (ref "R45") (pin "2") (pinfunction "2_2") (pintype "passive"))
      (node (ref "R47") (pin "2") (pinfunction "2_2") (pintype "passive"))
      (node (ref "R48") (pin "2") (pinfunction "2_2") (pintype "passive"))
      (node (ref "SD1") (pin "4") (pinfunction "VDD_4") (pintype "power_in"))
    )
    (net (code "40") (name "Net-(SW2-P)") (class "Default")
      (node (ref "R10") (pin "2") (pinfunction "2_2") (pintype "passive"))
      (node (ref "R8") (pin "2") (pinfunction "2_2") (pintype "passive"))
      (node (ref "SW2") (pin "1") (pinfunction "P_1") (pintype "passive"))
    )
    (net (code "41") (name "Net-(SW3-S)") (class "Default")
      (node (ref "R12") (pin "1") (pinfunction "1_1") (pintype "passive"))
      (node (ref "SW3") (pin "2") (pinfunction "S_2") (pintype "passive"))
    )
    (net (code "42") (name "Net-(SW4-S)") (class "Default")
      (node (ref "R13") (pin "1") (pinfunction "1_1") (pintype "passive"))
      (node (ref "SW4") (pin "2") (pinfunction "S_2") (pintype "passive"))
    )
    (net (code "43") (name "Net-(SW5-S)") (class "Default")
      (node (ref "R14") (pin "1") (pinfunction "1_1") (pintype "passive"))
      (node (ref "SW5") (pin "2") (pinfunction "S_2") (pintype "passive"))
    )
    (net (code "44") (name "OSC32_IN") (class "Default")
      (node (ref "C4") (pin "1") (pinfunction "1_1") (pintype "passive"))
      (node (ref "IC2") (pin "3") (pinfunction "PC14/OSC32_IN_3") (pintype "bidirectional"))
      (node (ref "Q1") (pin "2") (pinfunction "2_2") (pintype "passive"))
    )
    (net (code "45") (name "OSC32_OUT") (class "Default")
      (node (ref "C5") (pin "1") (pinfunction "1_1") (pintype "passive"))
      (node (ref "IC2") (pin "4") (pinfunction "PC15/OSC32_OUT_4") (pintype "bidirectional"))
      (node (ref "Q1") (pin "1") (pinfunction "1_1") (pintype "passive"))
    )
    (net (code "46") (name "OSC_IN") (class "Default")
      (node (ref "C6") (pin "1") (pinfunction "1_1") (pintype "passive"))
      (node (ref "IC2") (pin "5") (pinfunction "OSC_IN/(PD0/CANRX)_5") (pintype "input"))
      (node (ref "Q2") (pin "1") (pinfunction "1_1") (pintype "passive"))
      (node (ref "R15") (pin "2") (pinfunction "2_2") (pintype "passive"))
    )
    (net (code "47") (name "OSC_OUT") (class "Default")
      (node (ref "C7") (pin "1") (pinfunction "1_1") (pintype "passive"))
      (node (ref "IC2") (pin "6") (pinfunction "OSC_OUT/(PD1/CANTX)_6") (pintype "output"))
      (node (ref "Q2") (pin "2") (pinfunction "2_2") (pintype "passive"))
      (node (ref "R15") (pin "1") (pinfunction "1_1") (pintype "passive"))
    )
    (net (code "48") (name "PA0") (class "Default")
      (node (ref "C24") (pin "2") (pinfunction "2_2") (pintype "passive"))
      (node (ref "IC2") (pin "14") (pinfunction "PA0/WKUP/USART2_CTS/ADC12_IN0/TIM2_CH1_ETR_14") (pintype "bidirectional"))
      (node (ref "R12") (pin "2") (pinfunction "2_2") (pintype "passive"))
      (node (ref "R13") (pin "2") (pinfunction "2_2") (pintype "passive"))
      (node (ref "R14") (pin "2") (pinfunction "2_2") (pintype "passive"))
      (node (ref "R16") (pin "2") (pinfunction "2_2") (pintype "passive"))
      (node (ref "STAMP") (pin "39") (pinfunction "19_39") (pintype "passive"))
    )
    (net (code "49") (name "PA1") (class "Default")
      (node (ref "IC2") (pin "15") (pinfunction "PA1/USART2_RTS/ADC12_IN1/TIM2_CH2_15") (pintype "bidirectional"))
      (node (ref "R19") (pin "1") (pinfunction "1_1") (pintype "passive"))
      (node (ref "STAMP") (pin "38") (pinfunction "18_38") (pintype "passive"))
    )
    (net (code "50") (name "PA2") (class "Default")
      (node (ref "IC2") (pin "16") (pinfunction "PA2/USART2_TX/ADC12_IN2/TIM2_CH3_16") (pintype "bidirectional"))
      (node (ref "R17") (pin "1") (pinfunction "1_1") (pintype "passive"))
      (node (ref "STAMP") (pin "37") (pinfunction "17_37") (pintype "passive"))
    )
    (net (code "51") (name "PA3") (class "Default")
      (node (ref "IC2") (pin "17") (pinfunction "PA3/USART2_RX/ADC12_IN3/TIM2_CH4_17") (pintype "bidirectional"))
      (node (ref "STAMP") (pin "36") (pinfunction "16_36") (pintype "passive"))
    )
    (net (code "52") (name "PA4") (class "Default")
      (node (ref "IC2") (pin "20") (pinfunction "PA4/SPI1_NSS/ADC12_IN4/USART2_CK_20") (pintype "bidirectional"))
      (node (ref "R18") (pin "1") (pinfunction "1_1") (pintype "passive"))
      (node (ref "STAMP") (pin "35") (pinfunction "15_35") (pintype "passive"))
    )
    (net (code "53") (name "PA5") (class "Default")
      (node (ref "IC2") (pin "21") (pinfunction "PA5/SPI1_SCK/ADC12_IN5_21") (pintype "bidirectional"))
      (node (ref "STAMP") (pin "34") (pinfunction "14_34") (pintype "passive"))
    )
    (net (code "54") (name "PA6") (class "Default")
      (node (ref "IC2") (pin "22") (pinfunction "PA6/SPI1_MISO/ADC12_IN6/TIM3_CH1_22") (pintype "bidirectional"))
      (node (ref "STAMP") (pin "33") (pinfunction "13_33") (pintype "passive"))
    )
    (net (code "55") (name "PA7") (class "Default")
      (node (ref "IC2") (pin "23") (pinfunction "PA7SPI1_MOSI/ADC12_IN7/TIM3_CH2_23") (pintype "bidirectional"))
      (node (ref "STAMP") (pin "32") (pinfunction "12_32") (pintype "passive"))
    )
    (net (code "56") (name "PA8") (class "Default")
      (node (ref "IC2") (pin "41") (pinfunction "PA8/USART1_CK/MCO/TIM1_CH1_41") (pintype "bidirectional"))
      (node (ref "STAMP") (pin "25") (pinfunction "5_25") (pintype "passive"))
    )
    (net (code "57") (name "PA15") (class "Default")
      (node (ref "IC2") (pin "50") (pinfunction "JTDI/(TIM2_CH1_ETR/PA15/SPI1_NSS)_50") (pintype "bidirectional"))
      (node (ref "STAMP") (pin "24") (pinfunction "4_24") (pintype "passive"))
    )
    (net (code "58") (name "PB0") (class "Default")
      (node (ref "IC2") (pin "26") (pinfunction "PB0/ADC12_IN8/TIM3_CH3/(TIM1_CH2N)_26") (pintype "bidirectional"))
      (node (ref "R39") (pin "2") (pinfunction "2_2") (pintype "passive"))
    )
    (net (code "59") (name "PB1") (class "Default")
      (node (ref "IC2") (pin "27") (pinfunction "PB1/ADC12_IN9/TIM3_CH4/(TIM1_CH3N)_27") (pintype "bidirectional"))
      (node (ref "R40") (pin "2") (pinfunction "2_2") (pintype "passive"))
    )
    (net (code "60") (name "PB3") (class "Default")
      (node (ref "IC2") (pin "55") (pinfunction "JTDO/(TIM2_CH2/PB3/TRACESWO/SPI1_SCK)_55") (pintype "bidirectional"))
      (node (ref "STAMP") (pin "23") (pinfunction "3_23") (pintype "passive"))
    )
    (net (code "61") (name "PB4") (class "Default")
      (node (ref "IC2") (pin "56") (pinfunction "JTNRST/(PB4/TIM3_CH1/SPI1_MISO)_56") (pintype "bidirectional"))
      (node (ref "R22") (pin "2") (pinfunction "2_2") (pintype "passive"))
    )
    (net (code "62") (name "PC0") (class "Default")
      (node (ref "IC2") (pin "8") (pinfunction "PC0/ADC10_8") (pintype "bidirectional"))
      (node (ref "R33") (pin "2") (pinfunction "2_2") (pintype "passive"))
    )
    (net (code "63") (name "PC1") (class "Default")
      (node (ref "IC2") (pin "9") (pinfunction "PC1/ADC11_9") (pintype "bidirectional"))
      (node (ref "R34") (pin "2") (pinfunction "2_2") (pintype "passive"))
    )
    (net (code "64") (name "PC2") (class "Default")
      (node (ref "IC2") (pin "10") (pinfunction "PC2/ADC12_10") (pintype "bidirectional"))
      (node (ref "R35") (pin "2") (pinfunction "2_2") (pintype "passive"))
    )
    (net (code "65") (name "PC3") (class "Default")
      (node (ref "IC2") (pin "11") (pinfunction "PC3/ADC13_11") (pintype "bidirectional"))
      (node (ref "R36") (pin "2") (pinfunction "2_2") (pintype "passive"))
    )
    (net (code "66") (name "PC4") (class "Default")
      (node (ref "IC2") (pin "24") (pinfunction "PC4/ADC14_24") (pintype "bidirectional"))
      (node (ref "R37") (pin "2") (pinfunction "2_2") (pintype "passive"))
    )
    (net (code "67") (name "PC5") (class "Default")
      (node (ref "IC2") (pin "25") (pinfunction "PC5/ADC15_25") (pintype "bidirectional"))
      (node (ref "R38") (pin "2") (pinfunction "2_2") (pintype "passive"))
    )
    (net (code "68") (name "PC13") (class "Default")
      (node (ref "IC2") (pin "2") (pinfunction "PC13/TAMPER-RTC_2") (pintype "bidirectional"))
      (node (ref "STAMP") (pin "22") (pinfunction "2_22") (pintype "passive"))
    )
    (net (code "69") (name "RS485_A") (class "Default")
      (node (ref "F2") (pin "P$2") (pinfunction "2_P$2") (pintype "passive"))
      (node (ref "X1") (pin "2") (pinfunction "SK_2") (pintype "passive"))
    )
    (net (code "70") (name "RS485_B") (class "Default")
      (node (ref "F1") (pin "P$2") (pinfunction "2_P$2") (pintype "passive"))
      (node (ref "X1") (pin "1") (pinfunction "SK_1") (pintype "passive"))
    )
    (net (code "71") (name "RXD1") (class "Default")
      (node (ref "IC2") (pin "43") (pinfunction "PA10/USART1_RX/TIM1_CH3_43") (pintype "bidirectional"))
      (node (ref "JP1") (pin "3") (pinfunction "3_3") (pintype "passive"))
      (node (ref "R23") (pin "1") (pinfunction "1_1") (pintype "passive"))
    )
    (net (code "72") (name "RXD3") (class "Default")
      (node (ref "IC2") (pin "52") (pinfunction "PC11/(USART3_RX)_52") (pintype "bidirectional"))
      (node (ref "IC4") (pin "1") (pinfunction "RO_1") (pintype "output"))
    )
    (net (code "73") (name "SCL2") (class "Default")
      (node (ref "IC1") (pin "6") (pinfunction "SCL_6") (pintype "bidirectional"))
      (node (ref "IC2") (pin "29") (pinfunction "PB10/I2C2_SCL/USART3_TX/(TIM2_CH3)_29") (pintype "bidirectional"))
      (node (ref "R3") (pin "1") (pinfunction "1_1") (pintype "passive"))
      (node (ref "STAMP") (pin "31") (pinfunction "11_31") (pintype "passive"))
    )
    (net (code "74") (name "SDA2") (class "Default")
      (node (ref "IC1") (pin "5") (pinfunction "SDA_5") (pintype "bidirectional"))
      (node (ref "IC2") (pin "30") (pinfunction "PB11/I2C2_SDA/USART3_RX/(TIM2_CH4)_30") (pintype "bidirectional"))
      (node (ref "R4") (pin "1") (pinfunction "1_1") (pintype "passive"))
      (node (ref "STAMP") (pin "30") (pinfunction "10_30") (pintype "passive"))
    )
    (net (code "75") (name "SPI2_MISO") (class "Default")
      (node (ref "IC2") (pin "35") (pinfunction "PB14/SPI2_MISO/TIM1_CH2N/USART3_RTS_35") (pintype "bidirectional"))
      (node (ref "SD1") (pin "7") (pinfunction "DAT0(DO)_7") (pintype "bidirectional"))
      (node (ref "STAMP") (pin "27") (pinfunction "7_27") (pintype "passive"))
    )
    (net (code "76") (name "SPI2_MOSI") (class "Default")
      (node (ref "IC2") (pin "36") (pinfunction "PB15/SPI2_MOSI/TIM1_CH3N_36") (pintype "bidirectional"))
      (node (ref "SD1") (pin "3") (pinfunction "CMD(DI)_3") (pintype "bidirectional"))
      (node (ref "STAMP") (pin "26") (pinfunction "6_26") (pintype "passive"))
    )
    (net (code "77") (name "SPI2_NSS") (class "Default")
      (node (ref "IC2") (pin "33") (pinfunction "PB12/SPI2_NSS/I2C2_SMBAI/TIM1_BKIN/USART3_CK_33") (pintype "bidirectional"))
      (node (ref "STAMP") (pin "29") (pinfunction "9_29") (pintype "passive"))
    )
    (net (code "78") (name "SPI2_SCLK") (class "Default")
      (node (ref "IC2") (pin "34") (pinfunction "PB13/SPI2_SCK/TIM1_CH1N/USART3_CTS_34") (pintype "bidirectional"))
      (node (ref "SD1") (pin "5") (pinfunction "CLK(SCLK)_5") (pintype "input"))
      (node (ref "STAMP") (pin "28") (pinfunction "8_28") (pintype "passive"))
    )
    (net (code "79") (name "SWCLK") (class "Default")
      (node (ref "IC2") (pin "49") (pinfunction "JTCK-SWCLK/(PA14)_49") (pintype "bidirectional"))
      (node (ref "R1") (pin "1") (pinfunction "1_1") (pintype "passive"))
      (node (ref "SWD1") (pin "2") (pinfunction "2_2") (pintype "passive"))
    )
    (net (code "80") (name "SWDIO") (class "Default")
      (node (ref "IC2") (pin "46") (pinfunction "JTMS-SWDIO/(PA13)_46") (pintype "bidirectional"))
      (node (ref "R2") (pin "1") (pinfunction "1_1") (pintype "passive"))
      (node (ref "SWD1") (pin "4") (pinfunction "4_4") (pintype "passive"))
    )
    (net (code "81") (name "TIM3_CH1") (class "Default")
      (node (ref "IC2") (pin "37") (pinfunction "PC6/(TIM3_CH1)_37") (pintype "bidirectional"))
      (node (ref "R25") (pin "2") (pinfunction "2_2") (pintype "passive"))
    )
    (net (code "82") (name "TIM3_CH2") (class "Default")
      (node (ref "IC2") (pin "38") (pinfunction "PC7/(TIM3_CH2)_38") (pintype "bidirectional"))
      (node (ref "R26") (pin "2") (pinfunction "2_2") (pintype "passive"))
    )
    (net (code "83") (name "TIM3_CH3") (class "Default")
      (node (ref "IC2") (pin "39") (pinfunction "PC8/(TIM3_CH3)_39") (pintype "bidirectional"))
      (node (ref "R27") (pin "2") (pinfunction "2_2") (pintype "passive"))
    )
    (net (code "84") (name "TIM3_CH4") (class "Default")
      (node (ref "IC2") (pin "40") (pinfunction "PC9/(TIM3_CH4)_40") (pintype "bidirectional"))
      (node (ref "R28") (pin "2") (pinfunction "2_2") (pintype "passive"))
    )
    (net (code "85") (name "TIM4_CH1") (class "Default")
      (node (ref "IC2") (pin "58") (pinfunction "PB6/I2C1_SCL/TIM4_CH1/(USART1_TX)_58") (pintype "bidirectional"))
      (node (ref "R29") (pin "2") (pinfunction "2_2") (pintype "passive"))
    )
    (net (code "86") (name "TIM4_CH2") (class "Default")
      (node (ref "IC2") (pin "59") (pinfunction "PB7/I2C1_SDA/TIM4_CH2/(USART1_RX)_59") (pintype "bidirectional"))
      (node (ref "R30") (pin "2") (pinfunction "2_2") (pintype "passive"))
    )
    (net (code "87") (name "TIM4_CH3") (class "Default")
      (node (ref "IC2") (pin "61") (pinfunction "PB8/TIM4_CH3/(I2C1_SCL/CANRX)_61") (pintype "bidirectional"))
      (node (ref "R31") (pin "2") (pinfunction "2_2") (pintype "passive"))
    )
    (net (code "88") (name "TIM4_CH4") (class "Default")
      (node (ref "IC2") (pin "62") (pinfunction "PB9/TIM4_CH4/(I2C1_SDA/CANTX)_62") (pintype "bidirectional"))
      (node (ref "R32") (pin "2") (pinfunction "2_2") (pintype "passive"))
    )
    (net (code "89") (name "TXD1") (class "Default")
      (node (ref "IC2") (pin "42") (pinfunction "PA9/USART1_TX/TIM1_CH2_42") (pintype "bidirectional"))
      (node (ref "JP1") (pin "2") (pinfunction "2_2") (pintype "passive"))
    )
    (net (code "90") (name "TXD3") (class "Default")
      (node (ref "IC2") (pin "51") (pinfunction "PC10/(USART3_TX)_51") (pintype "bidirectional"))
      (node (ref "IC4") (pin "2") (pinfunction "RE/_2") (pintype "input"))
      (node (ref "IC4") (pin "3") (pinfunction "DE_3") (pintype "input"))
      (node (ref "R41") (pin "2") (pinfunction "2_2") (pintype "passive"))
    )
    (net (code "91") (name "USB_DM") (class "Default")
      (node (ref "C18") (pin "1") (pinfunction "1_1") (pintype "passive"))
      (node (ref "IC2") (pin "44") (pinfunction "PA11/CANRX/USBDM/USART1_CTS/TIM1_CH4_44") (pintype "bidirectional"))
      (node (ref "R50") (pin "2") (pinfunction "2_2") (pintype "passive"))
    )
    (net (code "92") (name "USB_DP") (class "Default")
      (node (ref "C19") (pin "1") (pinfunction "1_1") (pintype "passive"))
      (node (ref "IC2") (pin "45") (pinfunction "PA12/CANTX/USBDP/USART1_RTS/TIM1_ETR_45") (pintype "bidirectional"))
      (node (ref "R42") (pin "1") (pinfunction "1_1") (pintype "passive"))
      (node (ref "R49") (pin "2") (pinfunction "2_2") (pintype "passive"))
    )
    (net (code "93") (name "VBAT") (class "Default")
      (node (ref "G1") (pin "+") (pinfunction "+_+") (pintype "passive"))
      (node (ref "IC2") (pin "1") (pinfunction "VBAT_1") (pintype "power_in"))
    )
    (net (code "94") (name "VDDA") (class "Default")
      (node (ref "C11") (pin "1") (pinfunction "1_1") (pintype "passive"))
      (node (ref "C24") (pin "1") (pinfunction "1_1") (pintype "passive"))
      (node (ref "IC2") (pin "13") (pinfunction "VDDA_13") (pintype "power_in"))
      (node (ref "L1") (pin "2") (pinfunction "2_2") (pintype "passive"))
      (node (ref "SW3") (pin "1") (pinfunction "P_1") (pintype "passive"))
      (node (ref "SW4") (pin "1") (pinfunction "P_1") (pintype "passive"))
      (node (ref "SW5") (pin "1") (pinfunction "P_1") (pintype "passive"))
    )
    (net (code "95") (name "unconnected-(SWD1-Pad6)") (class "Default")
      (node (ref "SWD1") (pin "6") (pinfunction "6_6") (pintype "passive"))
    )
    (net (code "96") (name "unconnected-(U1-MASS-Pad4)") (class "Default")
      (node (ref "U1") (pin "4") (pinfunction "MASS_4") (pintype "passive"))
    )
    (net (code "97") (name "~{LCD_CS}") (class "Default")
      (node (ref "LCD1") (pin "2") (pinfunction "~{CS}_2") (pintype "input"))
      (node (ref "R19") (pin "2") (pinfunction "2_2") (pintype "passive"))
      (node (ref "R20") (pin "1") (pinfunction "1_1") (pintype "passive"))
    )
    (net (code "98") (name "~{RESET}") (class "Default")
      (node (ref "C3") (pin "1") (pinfunction "1_1") (pintype "passive"))
      (node (ref "IC2") (pin "7") (pinfunction "~{RESET}_7") (pintype "input"))
      (node (ref "LCD1") (pin "1") (pinfunction "~{RST}_1") (pintype "input"))
      (node (ref "R11") (pin "1") (pinfunction "1_1") (pintype "passive"))
      (node (ref "SW1") (pin "2") (pinfunction "S_2") (pintype "passive"))
      (node (ref "SWD1") (pin "5") (pinfunction "5_5") (pintype "passive"))
    )
    (net (code "99") (name "~{SD_CS}") (class "Default")
      (node (ref "IC2") (pin "54") (pinfunction "PD2/TIM3_ETR_54") (pintype "bidirectional"))
      (node (ref "R43") (pin "1") (pinfunction "1_1") (pintype "passive"))
      (node (ref "SD1") (pin "2") (pinfunction "CD/DAT3(~{CS})_2") (pintype "bidirectional"))
    )
    (net (code "100") (name "~{SD_DET}") (class "Default")
      (node (ref "R45") (pin "1") (pinfunction "1_1") (pintype "passive"))
      (node (ref "SD1") (pin "9") (pinfunction "~{CARD}_9") (pintype "passive"))
    )
    (net (code "101") (name "~{USB_DIS}") (class "Default")
      (node (ref "IC2") (pin "57") (pinfunction "PB5/I2C1_SMBA/(TIM3_CH2/SPI1_MOSI)_57") (pintype "bidirectional"))
      (node (ref "R7") (pin "1") (pinfunction "1_1") (pintype "passive"))
    )
  )
)
